# ESP8266_ESP-01_Breakout.net
KiCad netlist of a schematic drawn in EAGLE
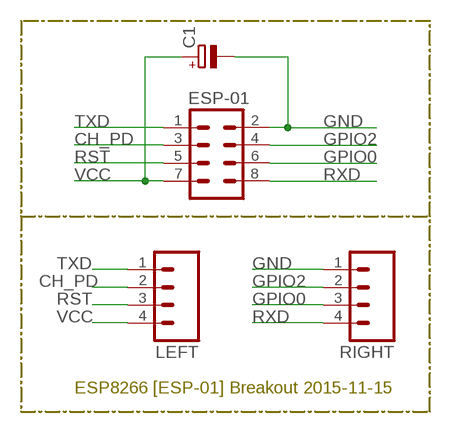
[diagram p0: schematic, sheet 1]

(export (version "E")
  (design (tool "Eeschema 10.0.6"))
  (components
    (comp (ref "C1")
      (value "CPOL-EUB45181B")
      (footprint "eagle-import:B45181B")
      (libsource (lib "eagle-import") (part "CPOL-EUB45181B"))
    )
    (comp (ref "ESP-01")
      (value "M04X2")
      (footprint "eagle-import:2X4")
      (libsource (lib "eagle-import") (part "M04X2"))
    )
    (comp (ref "LEFT")
      (value "M04PTH")
      (footprint "eagle-import:1X04")
      (libsource (lib "eagle-import") (part "M04PTH"))
    )
    (comp (ref "RIGHT")
      (value "M04PTH")
      (footprint "eagle-import:1X04")
      (libsource (lib "eagle-import") (part "M04PTH"))
    )
  )
  (nets
    (net (code "1") (name "/CH_PD") (class "Default")
      (node (ref "ESP-01") (pin "3") (pinfunction "3_3") (pintype "passive"))
      (node (ref "LEFT") (pin "2") (pinfunction "2_2") (pintype "passive"))
    )
    (net (code "2") (name "/GND") (class "Default")
      (node (ref "C1") (pin "-") (pinfunction "-_-") (pintype "passive"))
      (node (ref "ESP-01") (pin "2") (pinfunction "2_2") (pintype "passive"))
      (node (ref "RIGHT") (pin "1") (pinfunction "1_1") (pintype "passive"))
    )
    (net (code "3") (name "/GPIO0") (class "Default")
      (node (ref "ESP-01") (pin "6") (pinfunction "6_6") (pintype "passive"))
      (node (ref "RIGHT") (pin "3") (pinfunction "3_3") (pintype "passive"))
    )
    (net (code "4") (name "/GPIO2") (class "Default")
      (node (ref "ESP-01") (pin "4") (pinfunction "4_4") (pintype "passive"))
      (node (ref "RIGHT") (pin "2") (pinfunction "2_2") (pintype "passive"))
    )
    (net (code "5") (name "/RST") (class "Default")
      (node (ref "ESP-01") (pin "5") (pinfunction "5_5") (pintype "passive"))
      (node (ref "LEFT") (pin "3") (pinfunction "3_3") (pintype "passive"))
    )
    (net (code "6") (name "/RXD") (class "Default")
      (node (ref "ESP-01") (pin "8") (pinfunction "8_8") (pintype "passive"))
      (node (ref "RIGHT") (pin "4") (pinfunction "4_4") (pintype "passive"))
    )
    (net (code "7") (name "/TXD") (class "Default")
      (node (ref "ESP-01") (pin "1") (pinfunction "1_1") (pintype "passive"))
      (node (ref "LEFT") (pin "1") (pinfunction "1_1") (pintype "passive"))
    )
    (net (code "8") (name "/VCC") (class "Default")
      (node (ref "C1") (pin "+") (pinfunction "+_+") (pintype "passive"))
      (node (ref "ESP-01") (pin "7") (pinfunction "7_7") (pintype "passive"))
      (node (ref "LEFT") (pin "4") (pinfunction "4_4") (pintype "passive"))
    )
  )
)
